# main.net
KiCad netlist of a schematic drawn in EAGLE
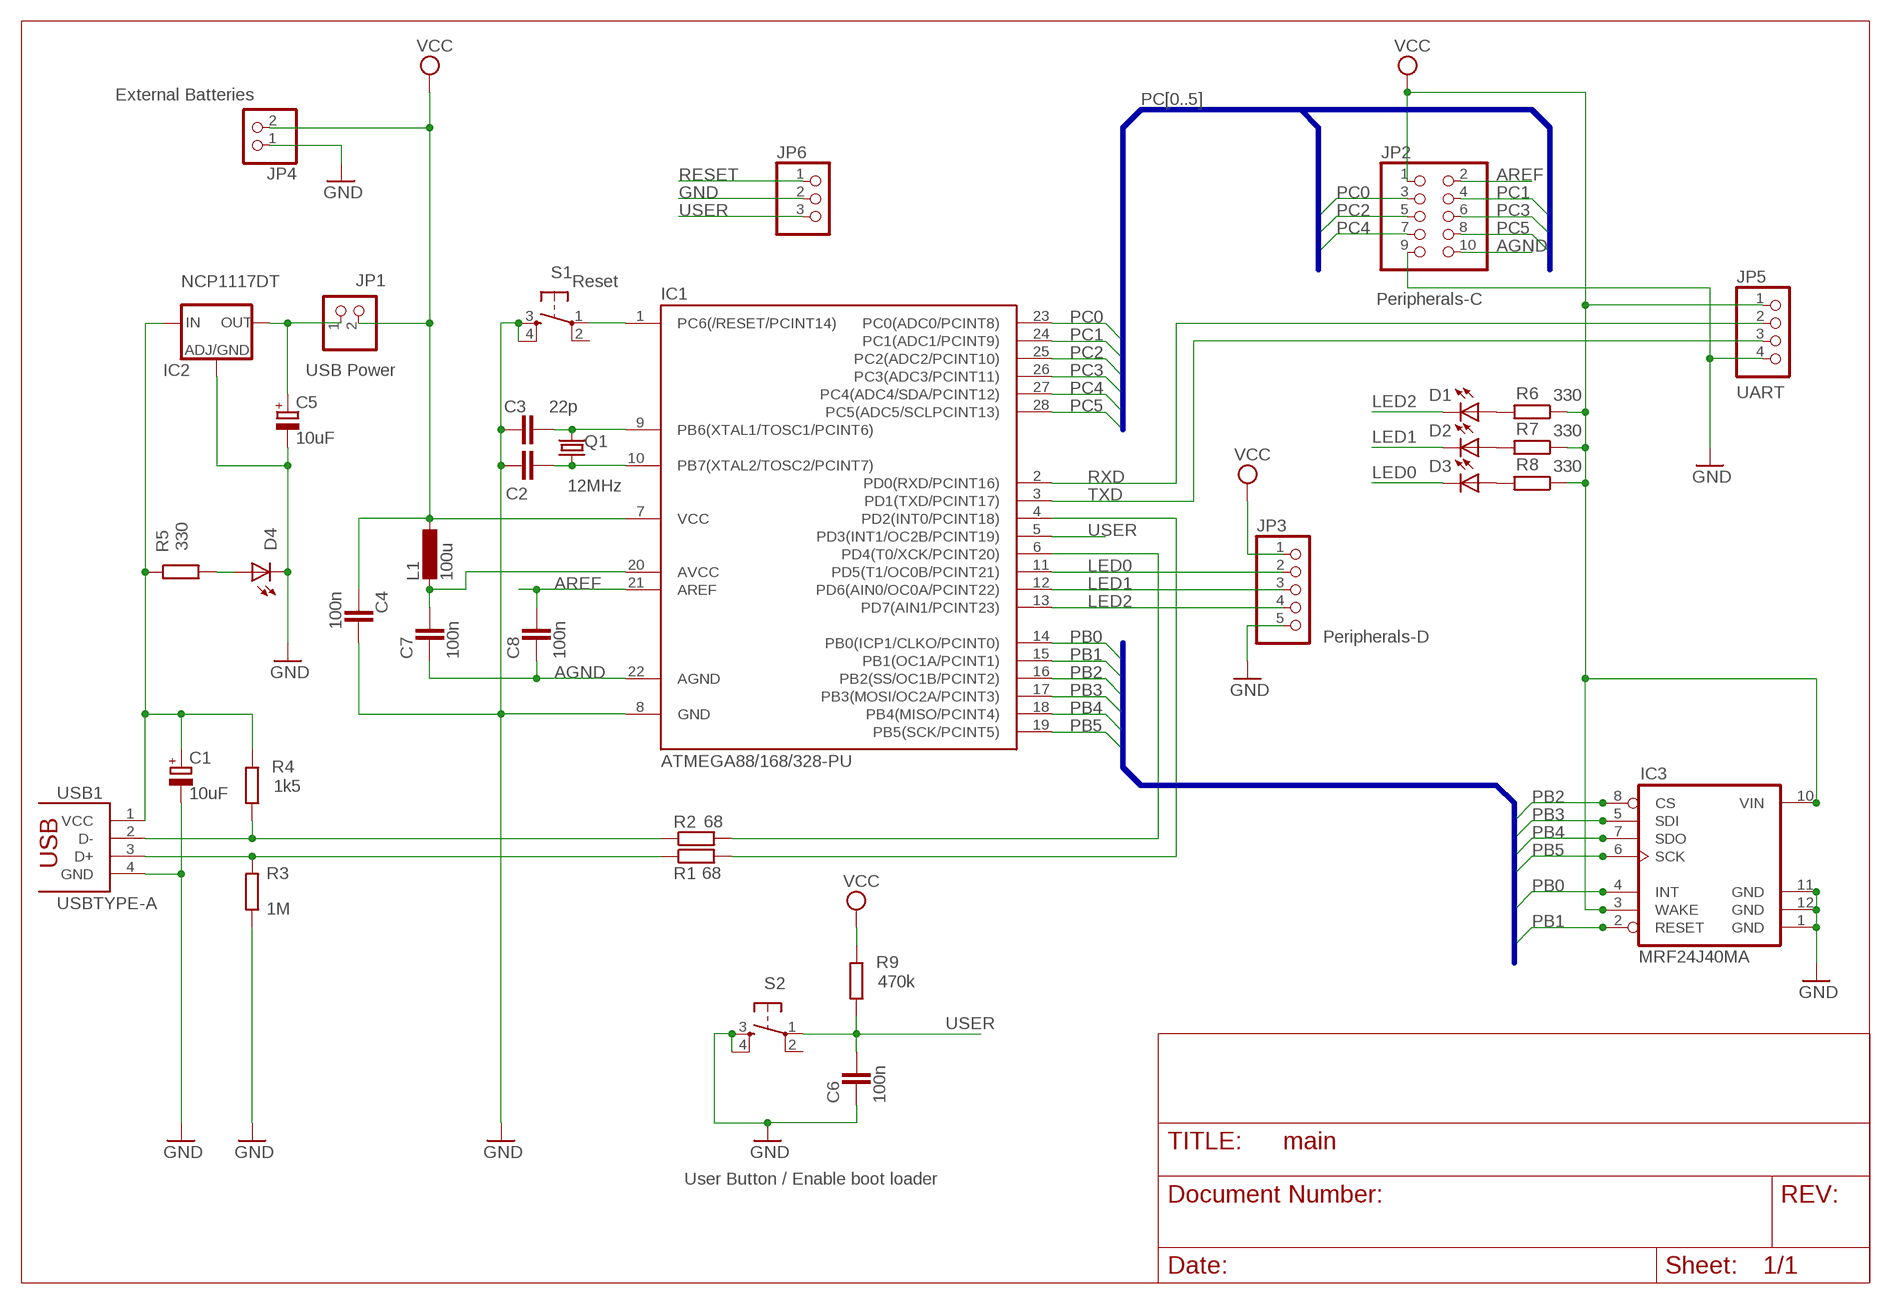
[diagram p0: schematic, sheet 1]

(export (version "E")
  (design (tool "Eeschema 10.0.6"))
  (components
    (comp (ref "C1")
      (value "10uF")
      (footprint "eagle-import:E2,5-6E")
      (libsource (lib "eagle-import") (part "CPOL-EUE2,5-6E"))
    )
    (comp (ref "C2")
      (value "22p")
      (footprint "eagle-import:C025-024X044")
      (libsource (lib "eagle-import") (part "C-EU025-024X044"))
    )
    (comp (ref "C3")
      (value "22p")
      (footprint "eagle-import:C025-024X044")
      (libsource (lib "eagle-import") (part "C-EU025-024X044"))
    )
    (comp (ref "C4")
      (value "100n")
      (footprint "eagle-import:C050-024X044")
      (libsource (lib "eagle-import") (part "C-EU050-024X044"))
    )
    (comp (ref "C5")
      (value "10uF")
      (footprint "eagle-import:E2,5-6E")
      (libsource (lib "eagle-import") (part "CPOL-EUE2,5-6E"))
    )
    (comp (ref "C6")
      (value "100n")
      (footprint "eagle-import:C050-024X044")
      (libsource (lib "eagle-import") (part "C-EU050-024X044"))
    )
    (comp (ref "C7")
      (value "100n")
      (footprint "eagle-import:C050-024X044")
      (libsource (lib "eagle-import") (part "C-EU050-024X044"))
    )
    (comp (ref "C8")
      (value "100n")
      (footprint "eagle-import:C050-024X044")
      (libsource (lib "eagle-import") (part "C-EU050-024X044"))
    )
    (comp (ref "D1")
      (value "LED3MM")
      (footprint "eagle-import:LED3MM")
      (libsource (lib "eagle-import") (part "LED3MM"))
    )
    (comp (ref "D2")
      (value "LED3MM")
      (footprint "eagle-import:LED3MM")
      (libsource (lib "eagle-import") (part "LED3MM"))
    )
    (comp (ref "D3")
      (value "LED3MM")
      (footprint "eagle-import:LED3MM")
      (libsource (lib "eagle-import") (part "LED3MM"))
    )
    (comp (ref "D4")
      (value "LED3MM")
      (footprint "eagle-import:LED3MM")
      (libsource (lib "eagle-import") (part "LED3MM"))
    )
    (comp (ref "IC1")
      (value "ATMEGA88/168/328-PU")
      (footprint "eagle-import:DIL28-3")
      (libsource (lib "eagle-import") (part "ATMEGA48/88/168-PU"))
    )
    (comp (ref "IC2")
      (value "NCP1117DT")
      (footprint "eagle-import:DPACK")
      (libsource (lib "eagle-import") (part "NCP1117DT"))
    )
    (comp (ref "IC3")
      (value "MRF24J40MA/B/C")
      (footprint "eagle-import:MRF24J40MAB-TH")
      (libsource (lib "eagle-import") (part "MRF24J40MAB"))
    )
    (comp (ref "JP1")
      (value "PINHD-1X2")
      (footprint "eagle-import:1X02")
      (libsource (lib "eagle-import") (part "PINHD-1X2"))
    )
    (comp (ref "JP2")
      (value "HEADER-2X5")
      (footprint "eagle-import:2X05")
      (libsource (lib "eagle-import") (part "HEADER-2X5"))
    )
    (comp (ref "JP3")
      (value "PINHD-1X5")
      (footprint "eagle-import:1X05")
      (libsource (lib "eagle-import") (part "PINHD-1X5"))
    )
    (comp (ref "JP4")
      (value "PINHD-1X2")
      (footprint "eagle-import:1X02")
      (libsource (lib "eagle-import") (part "PINHD-1X2"))
    )
    (comp (ref "JP5")
      (value "HEADER-1X4ROUND")
      (footprint "eagle-import:1X04_ROUND")
      (libsource (lib "eagle-import") (part "HEADER-1X4ROUND"))
    )
    (comp (ref "JP6")
      (value "PINHD-1X3")
      (footprint "eagle-import:1X03")
      (libsource (lib "eagle-import") (part "PINHD-1X3"))
    )
    (comp (ref "L1")
      (value "100u")
      (footprint "eagle-import:0207_7")
      (libsource (lib "eagle-import") (part "L-EU0207/7"))
    )
    (comp (ref "Q1")
      (value "12MHz")
      (footprint "eagle-import:HC49_S")
      (libsource (lib "eagle-import") (part "CRYSTALHC49S"))
    )
    (comp (ref "R1")
      (value "68")
      (footprint "eagle-import:0204_5@1")
      (libsource (lib "eagle-import") (part "R-EU_0204/5"))
    )
    (comp (ref "R2")
      (value "68")
      (footprint "eagle-import:0204_5@1")
      (libsource (lib "eagle-import") (part "R-EU_0204/5"))
    )
    (comp (ref "R3")
      (value "1M")
      (footprint "eagle-import:0204_5@1")
      (libsource (lib "eagle-import") (part "R-EU_0204/5"))
    )
    (comp (ref "R4")
      (value "1k5")
      (footprint "eagle-import:0204_5@1")
      (libsource (lib "eagle-import") (part "R-EU_0204/5"))
    )
    (comp (ref "R5")
      (value "330")
      (footprint "eagle-import:0204_7@1")
      (libsource (lib "eagle-import") (part "R-EU_0204/7"))
    )
    (comp (ref "R6")
      (value "330")
      (footprint "eagle-import:0204_5@1")
      (libsource (lib "eagle-import") (part "R-EU_0204/5"))
    )
    (comp (ref "R7")
      (value "330")
      (footprint "eagle-import:0204_5@1")
      (libsource (lib "eagle-import") (part "R-EU_0204/5"))
    )
    (comp (ref "R8")
      (value "330")
      (footprint "eagle-import:0204_5@1")
      (libsource (lib "eagle-import") (part "R-EU_0204/5"))
    )
    (comp (ref "R9")
      (value "470k")
      (footprint "eagle-import:0204_5@1")
      (libsource (lib "eagle-import") (part "R-EU_0204/5"))
    )
    (comp (ref "S1")
      (value "DTS-6")
      (footprint "eagle-import:DTS-6")
      (libsource (lib "eagle-import") (part "DTS-6"))
    )
    (comp (ref "S2")
      (value "DTS-6")
      (footprint "eagle-import:DTS-6")
      (libsource (lib "eagle-import") (part "DTS-6"))
    )
    (comp (ref "USB1")
      (value "USBTYPE-A")
      (footprint "eagle-import:USBTYPE-A")
      (libsource (lib "eagle-import") (part "USBTYPE-A"))
    )
  )
  (nets
    (net (code "1") (name "/AGND") (class "Default")
      (node (ref "C7") (pin "1") (pinfunction "1_1") (pintype "passive"))
      (node (ref "C8") (pin "1") (pinfunction "1_1") (pintype "passive"))
      (node (ref "IC1") (pin "22") (pinfunction "AGND_22") (pintype "power_in"))
      (node (ref "JP2") (pin "10") (pinfunction "10_10") (pintype "passive"))
    )
    (net (code "2") (name "/AREF") (class "Default")
      (node (ref "C8") (pin "2") (pinfunction "2_2") (pintype "passive"))
      (node (ref "IC1") (pin "21") (pinfunction "AREF_21") (pintype "passive"))
      (node (ref "JP2") (pin "2") (pinfunction "2_2") (pintype "passive"))
    )
    (net (code "3") (name "/LED0") (class "Default")
      (node (ref "D3") (pin "K") (pinfunction "C_K") (pintype "passive"))
      (node (ref "IC1") (pin "11") (pinfunction "PD5(T1/OC0B/PCINT21)_11") (pintype "bidirectional"))
      (node (ref "JP3") (pin "2") (pinfunction "2_2") (pintype "passive"))
    )
    (net (code "4") (name "/LED1") (class "Default")
      (node (ref "D2") (pin "K") (pinfunction "C_K") (pintype "passive"))
      (node (ref "IC1") (pin "12") (pinfunction "PD6(AIN0/OC0A/PCINT22)_12") (pintype "bidirectional"))
      (node (ref "JP3") (pin "3") (pinfunction "3_3") (pintype "passive"))
    )
    (net (code "5") (name "/LED2") (class "Default")
      (node (ref "D1") (pin "K") (pinfunction "C_K") (pintype "passive"))
      (node (ref "IC1") (pin "13") (pinfunction "PD7(AIN1/PCINT23)_13") (pintype "bidirectional"))
      (node (ref "JP3") (pin "4") (pinfunction "4_4") (pintype "passive"))
    )
    (net (code "6") (name "/PB0") (class "Default")
      (node (ref "IC1") (pin "14") (pinfunction "PB0(ICP1/CLKO/PCINT0)_14") (pintype "bidirectional"))
      (node (ref "IC3") (pin "16") (pinfunction "INT_16") (pintype "output"))
      (node (ref "IC3") (pin "4") (pinfunction "INT_4") (pintype "output"))
    )
    (net (code "7") (name "/PB1") (class "Default")
      (node (ref "IC1") (pin "15") (pinfunction "PB1(OC1A/PCINT1)_15") (pintype "bidirectional"))
      (node (ref "IC3") (pin "14") (pinfunction "RESET_14") (pintype "input"))
      (node (ref "IC3") (pin "2") (pinfunction "RESET_2") (pintype "input"))
    )
    (net (code "8") (name "/PB2") (class "Default")
      (node (ref "IC1") (pin "16") (pinfunction "PB2(SS/OC1B/PCINT2)_16") (pintype "bidirectional"))
      (node (ref "IC3") (pin "20") (pinfunction "CS_20") (pintype "input"))
      (node (ref "IC3") (pin "8") (pinfunction "CS_8") (pintype "input"))
    )
    (net (code "9") (name "/PB3") (class "Default")
      (node (ref "IC1") (pin "17") (pinfunction "PB3(MOSI/OC2A/PCINT3)_17") (pintype "bidirectional"))
      (node (ref "IC3") (pin "17") (pinfunction "SDI_17") (pintype "input"))
      (node (ref "IC3") (pin "5") (pinfunction "SDI_5") (pintype "input"))
    )
    (net (code "10") (name "/PB4") (class "Default")
      (node (ref "IC1") (pin "18") (pinfunction "PB4(MISO/PCINT4)_18") (pintype "bidirectional"))
      (node (ref "IC3") (pin "19") (pinfunction "SDO_19") (pintype "output"))
      (node (ref "IC3") (pin "7") (pinfunction "SDO_7") (pintype "output"))
    )
    (net (code "11") (name "/PB5") (class "Default")
      (node (ref "IC1") (pin "19") (pinfunction "PB5(SCK/PCINT5)_19") (pintype "bidirectional"))
      (node (ref "IC3") (pin "18") (pinfunction "SCK_18") (pintype "input"))
      (node (ref "IC3") (pin "6") (pinfunction "SCK_6") (pintype "input"))
    )
    (net (code "12") (name "/PC0") (class "Default")
      (node (ref "IC1") (pin "23") (pinfunction "PC0(ADC0/PCINT8)_23") (pintype "bidirectional"))
      (node (ref "JP2") (pin "3") (pinfunction "3_3") (pintype "passive"))
    )
    (net (code "13") (name "/PC1") (class "Default")
      (node (ref "IC1") (pin "24") (pinfunction "PC1(ADC1/PCINT9)_24") (pintype "bidirectional"))
      (node (ref "JP2") (pin "4") (pinfunction "4_4") (pintype "passive"))
    )
    (net (code "14") (name "/PC2") (class "Default")
      (node (ref "IC1") (pin "25") (pinfunction "PC2(ADC2/PCINT10)_25") (pintype "bidirectional"))
      (node (ref "JP2") (pin "5") (pinfunction "5_5") (pintype "passive"))
    )
    (net (code "15") (name "/PC3") (class "Default")
      (node (ref "IC1") (pin "26") (pinfunction "PC3(ADC3/PCINT11)_26") (pintype "bidirectional"))
      (node (ref "JP2") (pin "6") (pinfunction "6_6") (pintype "passive"))
    )
    (net (code "16") (name "/PC4") (class "Default")
      (node (ref "IC1") (pin "27") (pinfunction "PC4(ADC4/SDA/PCINT12)_27") (pintype "bidirectional"))
      (node (ref "JP2") (pin "7") (pinfunction "7_7") (pintype "passive"))
    )
    (net (code "17") (name "/PC5") (class "Default")
      (node (ref "IC1") (pin "28") (pinfunction "PC5(ADC5/SCLPCINT13)_28") (pintype "bidirectional"))
      (node (ref "JP2") (pin "8") (pinfunction "8_8") (pintype "passive"))
    )
    (net (code "19") (name "/RESET") (class "Default")
      (node (ref "IC1") (pin "1") (pinfunction "PC6(/RESET/PCINT14)_1") (pintype "bidirectional"))
      (node (ref "JP6") (pin "1") (pinfunction "1_1") (pintype "passive"))
      (node (ref "S1") (pin "1") (pinfunction "1_1") (pintype "passive"))
    )
    (net (code "20") (name "/RXD") (class "Default")
      (node (ref "IC1") (pin "2") (pinfunction "PD0(RXD/PCINT16)_2") (pintype "bidirectional"))
      (node (ref "JP5") (pin "2") (pinfunction "2_2") (pintype "passive"))
    )
    (net (code "21") (name "/TXD") (class "Default")
      (node (ref "IC1") (pin "3") (pinfunction "PD1(TXD/PCINT17)_3") (pintype "bidirectional"))
      (node (ref "JP5") (pin "3") (pinfunction "3_3") (pintype "passive"))
    )
    (net (code "22") (name "/USER") (class "Default")
      (node (ref "C6") (pin "2") (pinfunction "2_2") (pintype "passive"))
      (node (ref "IC1") (pin "5") (pinfunction "PD3(INT1/OC2B/PCINT19)_5") (pintype "bidirectional"))
      (node (ref "JP6") (pin "3") (pinfunction "3_3") (pintype "passive"))
      (node (ref "R9") (pin "2") (pinfunction "2_2") (pintype "passive"))
      (node (ref "S2") (pin "1") (pinfunction "1_1") (pintype "passive"))
    )
    (net (code "23") (name "GND") (class "Default")
      (node (ref "C1") (pin "-") (pinfunction "-_-") (pintype "passive"))
      (node (ref "C2") (pin "1") (pinfunction "1_1") (pintype "passive"))
      (node (ref "C3") (pin "1") (pinfunction "1_1") (pintype "passive"))
      (node (ref "C4") (pin "2") (pinfunction "2_2") (pintype "passive"))
      (node (ref "C5") (pin "-") (pinfunction "-_-") (pintype "passive"))
      (node (ref "C6") (pin "1") (pinfunction "1_1") (pintype "passive"))
      (node (ref "D4") (pin "K") (pinfunction "C_K") (pintype "passive"))
      (node (ref "IC1") (pin "8") (pinfunction "GND_8") (pintype "power_in"))
      (node (ref "IC2") (pin "1") (pinfunction "ADJ_1") (pintype "input"))
      (node (ref "IC3") (pin "1") (pinfunction "GND_1") (pintype "power_in"))
      (node (ref "IC3") (pin "11") (pinfunction "GND_11") (pintype "power_in"))
      (node (ref "IC3") (pin "12") (pinfunction "GND_12") (pintype "power_in"))
      (node (ref "IC3") (pin "13") (pinfunction "GND_13") (pintype "power_in"))
      (node (ref "IC3") (pin "23") (pinfunction "GND_23") (pintype "power_in"))
      (node (ref "IC3") (pin "24") (pinfunction "GND_24") (pintype "power_in"))
      (node (ref "JP2") (pin "9") (pinfunction "9_9") (pintype "passive"))
      (node (ref "JP3") (pin "5") (pinfunction "5_5") (pintype "passive"))
      (node (ref "JP4") (pin "1") (pinfunction "1_1") (pintype "passive"))
      (node (ref "JP5") (pin "4") (pinfunction "4_4") (pintype "passive"))
      (node (ref "JP6") (pin "2") (pinfunction "2_2") (pintype "passive"))
      (node (ref "R3") (pin "1") (pinfunction "1_1") (pintype "passive"))
      (node (ref "S1") (pin "3") (pinfunction "3_3") (pintype "passive"))
      (node (ref "S1") (pin "4") (pinfunction "4_4") (pintype "passive"))
      (node (ref "S2") (pin "3") (pinfunction "3_3") (pintype "passive"))
      (node (ref "S2") (pin "4") (pinfunction "4_4") (pintype "passive"))
      (node (ref "USB1") (pin "4") (pinfunction "GND_4") (pintype "power_in"))
    )
    (net (code "24") (name "Net-(D1-PadA)") (class "Default")
      (node (ref "D1") (pin "A") (pinfunction "A_A") (pintype "passive"))
      (node (ref "R6") (pin "2") (pinfunction "2_2") (pintype "passive"))
    )
    (net (code "25") (name "Net-(D2-PadA)") (class "Default")
      (node (ref "D2") (pin "A") (pinfunction "A_A") (pintype "passive"))
      (node (ref "R7") (pin "2") (pinfunction "2_2") (pintype "passive"))
    )
    (net (code "26") (name "Net-(D3-PadA)") (class "Default")
      (node (ref "D3") (pin "A") (pinfunction "A_A") (pintype "passive"))
      (node (ref "R8") (pin "2") (pinfunction "2_2") (pintype "passive"))
    )
    (net (code "27") (name "Net-(D4-PadA)") (class "Default")
      (node (ref "D4") (pin "A") (pinfunction "A_A") (pintype "passive"))
      (node (ref "R5") (pin "2") (pinfunction "2_2") (pintype "passive"))
    )
    (net (code "28") (name "Net-(IC1-AVCC)") (class "Default")
      (node (ref "C7") (pin "2") (pinfunction "2_2") (pintype "passive"))
      (node (ref "IC1") (pin "20") (pinfunction "AVCC_20") (pintype "passive"))
      (node (ref "L1") (pin "1") (pinfunction "1_1") (pintype "passive"))
    )
    (net (code "29") (name "Net-(IC1-PB6(XTAL1{slash}TOSC1{slash}PCINT6))") (class "Default")
      (node (ref "C3") (pin "2") (pinfunction "2_2") (pintype "passive"))
      (node (ref "IC1") (pin "9") (pinfunction "PB6(XTAL1/TOSC1/PCINT6)_9") (pintype "bidirectional"))
      (node (ref "Q1") (pin "2") (pinfunction "2_2") (pintype "passive"))
    )
    (net (code "30") (name "Net-(IC1-PB7(XTAL2{slash}TOSC2{slash}PCINT7))") (class "Default")
      (node (ref "C2") (pin "2") (pinfunction "2_2") (pintype "passive"))
      (node (ref "IC1") (pin "10") (pinfunction "PB7(XTAL2/TOSC2/PCINT7)_10") (pintype "bidirectional"))
      (node (ref "Q1") (pin "1") (pinfunction "1_1") (pintype "passive"))
    )
    (net (code "31") (name "Net-(IC1-PD2(INT0{slash}PCINT18))") (class "Default")
      (node (ref "IC1") (pin "4") (pinfunction "PD2(INT0/PCINT18)_4") (pintype "bidirectional"))
      (node (ref "R1") (pin "2") (pinfunction "2_2") (pintype "passive"))
    )
    (net (code "32") (name "Net-(IC1-PD4(T0{slash}XCK{slash}PCINT20))") (class "Default")
      (node (ref "IC1") (pin "6") (pinfunction "PD4(T0/XCK/PCINT20)_6") (pintype "bidirectional"))
      (node (ref "R2") (pin "2") (pinfunction "2_2") (pintype "passive"))
    )
    (net (code "33") (name "Net-(IC2-IN)") (class "Default")
      (node (ref "C1") (pin "+") (pinfunction "+_+") (pintype "passive"))
      (node (ref "IC2") (pin "3") (pinfunction "IN_3") (pintype "input"))
      (node (ref "R4") (pin "1") (pinfunction "1_1") (pintype "passive"))
      (node (ref "R5") (pin "1") (pinfunction "1_1") (pintype "passive"))
      (node (ref "USB1") (pin "1") (pinfunction "VCC_1") (pintype "power_in"))
    )
    (net (code "34") (name "Net-(IC2-OUT)") (class "Default")
      (node (ref "C5") (pin "+") (pinfunction "+_+") (pintype "passive"))
      (node (ref "IC2") (pin "4") (pinfunction "OUT_4") (pintype "passive"))
      (node (ref "JP1") (pin "1") (pinfunction "1_1") (pintype "passive"))
    )
    (net (code "35") (name "Net-(USB1-D+)") (class "Default")
      (node (ref "R1") (pin "1") (pinfunction "1_1") (pintype "passive"))
      (node (ref "R3") (pin "2") (pinfunction "2_2") (pintype "passive"))
      (node (ref "USB1") (pin "3") (pinfunction "D+_3") (pintype "bidirectional"))
    )
    (net (code "36") (name "Net-(USB1-D-)") (class "Default")
      (node (ref "R2") (pin "1") (pinfunction "1_1") (pintype "passive"))
      (node (ref "R4") (pin "2") (pinfunction "2_2") (pintype "passive"))
      (node (ref "USB1") (pin "2") (pinfunction "D-_2") (pintype "bidirectional"))
    )
    (net (code "37") (name "VCC") (class "Default")
      (node (ref "C4") (pin "1") (pinfunction "1_1") (pintype "passive"))
      (node (ref "IC1") (pin "7") (pinfunction "VCC_7") (pintype "power_in"))
      (node (ref "IC3") (pin "10") (pinfunction "VIN_10") (pintype "power_in"))
      (node (ref "IC3") (pin "15") (pinfunction "WAKE_15") (pintype "input"))
      (node (ref "IC3") (pin "22") (pinfunction "VIN_22") (pintype "power_in"))
      (node (ref "IC3") (pin "3") (pinfunction "WAKE_3") (pintype "input"))
      (node (ref "JP1") (pin "2") (pinfunction "2_2") (pintype "passive"))
      (node (ref "JP2") (pin "1") (pinfunction "1_1") (pintype "passive"))
      (node (ref "JP3") (pin "1") (pinfunction "1_1") (pintype "passive"))
      (node (ref "JP4") (pin "2") (pinfunction "2_2") (pintype "passive"))
      (node (ref "JP5") (pin "1") (pinfunction "1_1") (pintype "passive"))
      (node (ref "L1") (pin "2") (pinfunction "2_2") (pintype "passive"))
      (node (ref "R6") (pin "1") (pinfunction "1_1") (pintype "passive"))
      (node (ref "R7") (pin "1") (pinfunction "1_1") (pintype "passive"))
      (node (ref "R8") (pin "1") (pinfunction "1_1") (pintype "passive"))
      (node (ref "R9") (pin "1") (pinfunction "1_1") (pintype "passive"))
    )
    (net (code "38") (name "unconnected-(S1-Pad2)") (class "Default")
      (node (ref "S1") (pin "2") (pinfunction "2_2") (pintype "passive"))
    )
    (net (code "39") (name "unconnected-(S2-Pad2)") (class "Default")
      (node (ref "S2") (pin "2") (pinfunction "2_2") (pintype "passive"))
    )
  )
)
